# Alimentacion_y_perifericos.net
KiCad netlist of a schematic drawn in Altium Designer
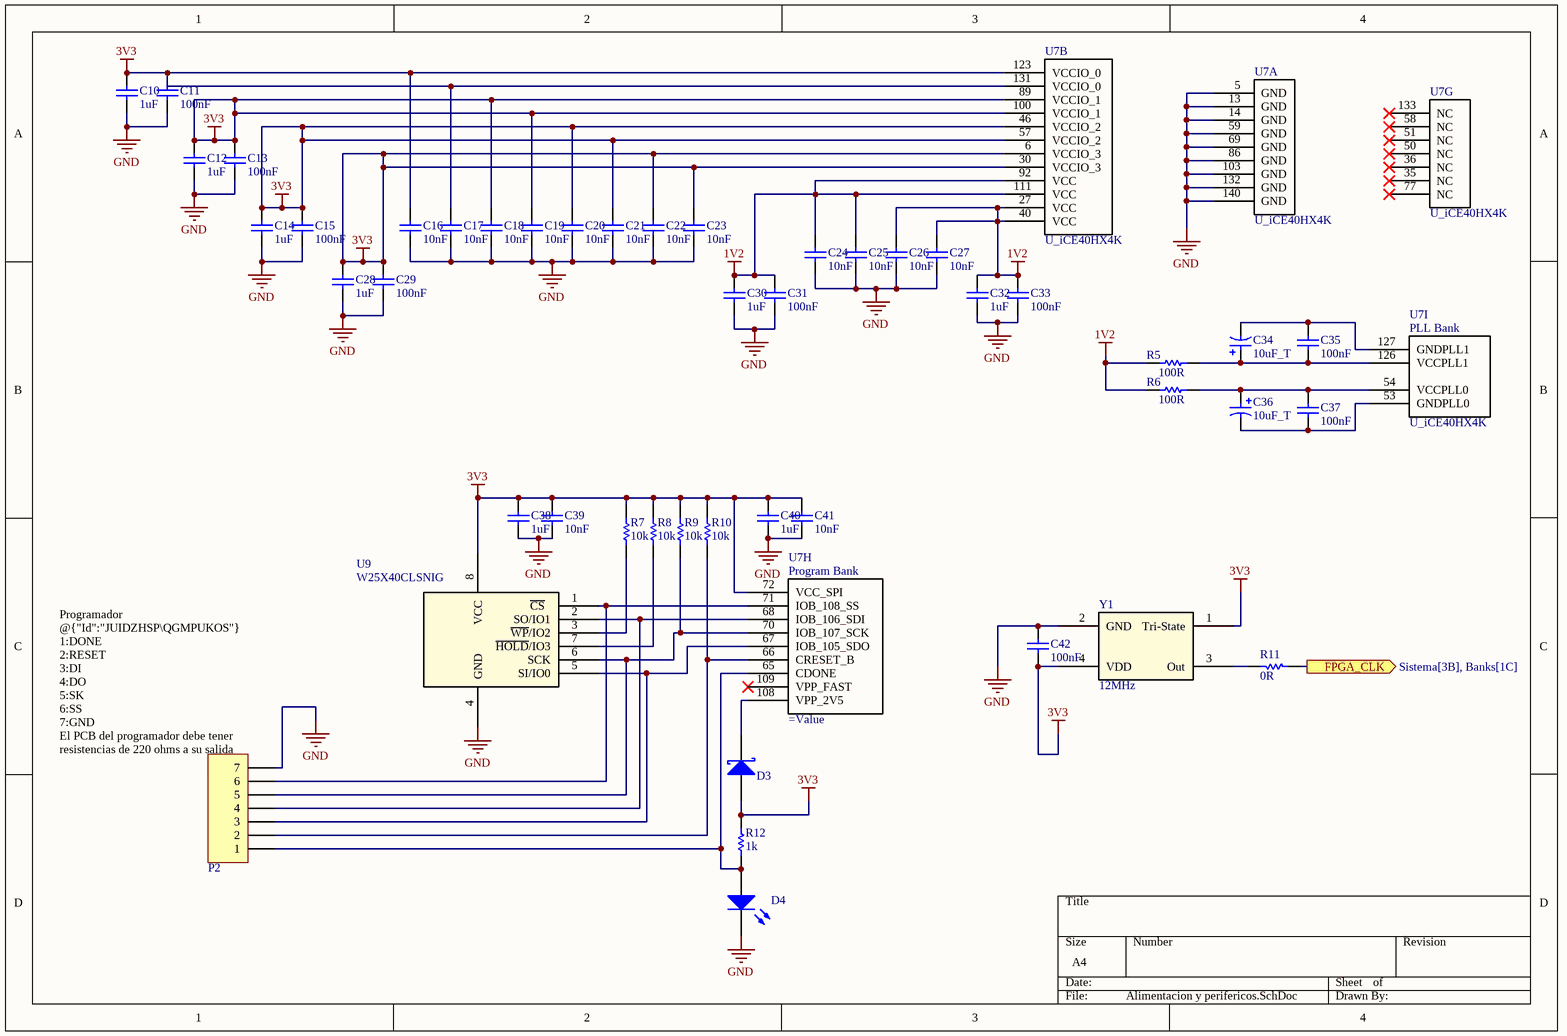
[diagram p0: Alimentacion y perifericos.SchDoc]

(export (version "E")
  (design (tool "Eeschema 10.0.6"))
  (components
    (comp (ref "C10")
      (value "1uF")
      (footprint "C_0805_2013_b")
      (description "Capacitor SMD 0805")
      (fields
        (field (name "MANUFACTURER") "Cal-Chip Electronics")
        (field (name "MANUFACTURER PART NUMBER") "GMC21X7R105K50NT")
      )
      (libsource (lib "MyLibraryV2") (part "C_1uF_50V_b"))
    )
    (comp (ref "C11")
      (value "100nF")
      (footprint "C_0805_2013_b")
      (description "Capacitor SMD 0805")
      (fields (field (name "TOLERANCE") "10%") (field (name "VOLTAGE") "50V"))
      (libsource (lib "MyLibraryV2") (part "C_100nF_50V_b"))
    )
    (comp (ref "C12")
      (value "1uF")
      (footprint "C_0805_2013_b")
      (description "Capacitor SMD 0805")
      (fields
        (field (name "MANUFACTURER") "Cal-Chip Electronics")
        (field (name "MANUFACTURER PART NUMBER") "GMC21X7R105K50NT")
      )
      (libsource (lib "MyLibraryV2") (part "C_1uF_50V_b"))
    )
    (comp (ref "C13")
      (value "100nF")
      (footprint "C_0805_2013_b")
      (description "Capacitor SMD 0805")
      (fields (field (name "TOLERANCE") "10%") (field (name "VOLTAGE") "50V"))
      (libsource (lib "MyLibraryV2") (part "C_100nF_50V_b"))
    )
    (comp (ref "C14")
      (value "1uF")
      (footprint "C_0805_2013_b")
      (description "Capacitor SMD 0805")
      (fields
        (field (name "MANUFACTURER") "Cal-Chip Electronics")
        (field (name "MANUFACTURER PART NUMBER") "GMC21X7R105K50NT")
      )
      (libsource (lib "MyLibraryV2") (part "C_1uF_50V_b"))
    )
    (comp (ref "C15")
      (value "100nF")
      (footprint "C_0805_2013_b")
      (description "Capacitor SMD 0805")
      (fields (field (name "TOLERANCE") "10%") (field (name "VOLTAGE") "50V"))
      (libsource (lib "MyLibraryV2") (part "C_100nF_50V_b"))
    )
    (comp (ref "C16")
      (value "10nF")
      (footprint "C_0805_2013_b")
      (description "Capacitor SMD 0805")
      (fields (field (name "TOLERANCE") "5%") (field (name "MANUFACTURER") "KEMET"))
      (libsource (lib "MyLibraryV2") (part "C_10nF_50V_b"))
    )
    (comp (ref "C17")
      (value "10nF")
      (footprint "C_0805_2013_b")
      (description "Capacitor SMD 0805")
      (fields (field (name "TOLERANCE") "5%") (field (name "MANUFACTURER") "KEMET"))
      (libsource (lib "MyLibraryV2") (part "C_10nF_50V_b"))
    )
    (comp (ref "C18")
      (value "10nF")
      (footprint "C_0805_2013_b")
      (description "Capacitor SMD 0805")
      (fields (field (name "TOLERANCE") "5%") (field (name "MANUFACTURER") "KEMET"))
      (libsource (lib "MyLibraryV2") (part "C_10nF_50V_b"))
    )
    (comp (ref "C19")
      (value "10nF")
      (footprint "C_0805_2013_b")
      (description "Capacitor SMD 0805")
      (fields (field (name "TOLERANCE") "5%") (field (name "MANUFACTURER") "KEMET"))
      (libsource (lib "MyLibraryV2") (part "C_10nF_50V_b"))
    )
    (comp (ref "C20")
      (value "10nF")
      (footprint "C_0805_2013_b")
      (description "Capacitor SMD 0805")
      (fields (field (name "TOLERANCE") "5%") (field (name "MANUFACTURER") "KEMET"))
      (libsource (lib "MyLibraryV2") (part "C_10nF_50V_b"))
    )
    (comp (ref "C21")
      (value "10nF")
      (footprint "C_0805_2013_b")
      (description "Capacitor SMD 0805")
      (fields (field (name "TOLERANCE") "5%") (field (name "MANUFACTURER") "KEMET"))
      (libsource (lib "MyLibraryV2") (part "C_10nF_50V_b"))
    )
    (comp (ref "C22")
      (value "10nF")
      (footprint "C_0805_2013_b")
      (description "Capacitor SMD 0805")
      (fields (field (name "TOLERANCE") "5%") (field (name "MANUFACTURER") "KEMET"))
      (libsource (lib "MyLibraryV2") (part "C_10nF_50V_b"))
    )
    (comp (ref "C23")
      (value "10nF")
      (footprint "C_0805_2013_b")
      (description "Capacitor SMD 0805")
      (fields (field (name "TOLERANCE") "5%") (field (name "MANUFACTURER") "KEMET"))
      (libsource (lib "MyLibraryV2") (part "C_10nF_50V_b"))
    )
    (comp (ref "C24")
      (value "10nF")
      (footprint "C_0805_2013_b")
      (description "Capacitor SMD 0805")
      (fields (field (name "TOLERANCE") "5%") (field (name "MANUFACTURER") "KEMET"))
      (libsource (lib "MyLibraryV2") (part "C_10nF_50V_b"))
    )
    (comp (ref "C25")
      (value "10nF")
      (footprint "C_0805_2013_b")
      (description "Capacitor SMD 0805")
      (fields (field (name "TOLERANCE") "5%") (field (name "MANUFACTURER") "KEMET"))
      (libsource (lib "MyLibraryV2") (part "C_10nF_50V_b"))
    )
    (comp (ref "C26")
      (value "10nF")
      (footprint "C_0805_2013_b")
      (description "Capacitor SMD 0805")
      (fields (field (name "TOLERANCE") "5%") (field (name "MANUFACTURER") "KEMET"))
      (libsource (lib "MyLibraryV2") (part "C_10nF_50V_b"))
    )
    (comp (ref "C27")
      (value "10nF")
      (footprint "C_0805_2013_b")
      (description "Capacitor SMD 0805")
      (fields (field (name "TOLERANCE") "5%") (field (name "MANUFACTURER") "KEMET"))
      (libsource (lib "MyLibraryV2") (part "C_10nF_50V_b"))
    )
    (comp (ref "C28")
      (value "1uF")
      (footprint "C_0805_2013_b")
      (description "Capacitor SMD 0805")
      (fields
        (field (name "MANUFACTURER") "Cal-Chip Electronics")
        (field (name "MANUFACTURER PART NUMBER") "GMC21X7R105K50NT")
      )
      (libsource (lib "MyLibraryV2") (part "C_1uF_50V_b"))
    )
    (comp (ref "C29")
      (value "100nF")
      (footprint "C_0805_2013_b")
      (description "Capacitor SMD 0805")
      (fields (field (name "TOLERANCE") "10%") (field (name "VOLTAGE") "50V"))
      (libsource (lib "MyLibraryV2") (part "C_100nF_50V_b"))
    )
    (comp (ref "C30")
      (value "1uF")
      (footprint "C_0805_2013_b")
      (description "Capacitor SMD 0805")
      (fields
        (field (name "MANUFACTURER") "Cal-Chip Electronics")
        (field (name "MANUFACTURER PART NUMBER") "GMC21X7R105K50NT")
      )
      (libsource (lib "MyLibraryV2") (part "C_1uF_50V_b"))
    )
    (comp (ref "C31")
      (value "100nF")
      (footprint "C_0805_2013_b")
      (description "Capacitor SMD 0805")
      (fields (field (name "TOLERANCE") "10%") (field (name "VOLTAGE") "50V"))
      (libsource (lib "MyLibraryV2") (part "C_100nF_50V_b"))
    )
    (comp (ref "C32")
      (value "1uF")
      (footprint "C_0805_2013_b")
      (description "Capacitor SMD 0805")
      (fields
        (field (name "MANUFACTURER") "Cal-Chip Electronics")
        (field (name "MANUFACTURER PART NUMBER") "GMC21X7R105K50NT")
      )
      (libsource (lib "MyLibraryV2") (part "C_1uF_50V_b"))
    )
    (comp (ref "C33")
      (value "100nF")
      (footprint "C_0805_2013_b")
      (description "Capacitor SMD 0805")
      (fields (field (name "TOLERANCE") "10%") (field (name "VOLTAGE") "50V"))
      (libsource (lib "MyLibraryV2") (part "C_100nF_50V_b"))
    )
    (comp (ref "C34")
      (value "10uF_T")
      (footprint "C_0805_2013_c")
      (description "Capacitor SMD 0805 Tant")
      (fields
        (field (name "MANUFACTURER") "Vishay")
        (field (name "MANUFACTURER PART NUMBER") "TMCP1A106MTRF")
      )
      (libsource (lib "MyLibraryV2") (part "C_10uF_10V_b"))
    )
    (comp (ref "C35")
      (value "100nF")
      (footprint "C_0805_2013_b")
      (description "Capacitor SMD 0805")
      (fields (field (name "TOLERANCE") "10%") (field (name "VOLTAGE") "50V"))
      (libsource (lib "MyLibraryV2") (part "C_100nF_50V_b"))
    )
    (comp (ref "C36")
      (value "10uF_T")
      (footprint "C_0805_2013_c")
      (description "Capacitor SMD 0805 Tant")
      (fields
        (field (name "MANUFACTURER") "Vishay")
        (field (name "MANUFACTURER PART NUMBER") "TMCP1A106MTRF")
      )
      (libsource (lib "MyLibraryV2") (part "C_10uF_10V_b"))
    )
    (comp (ref "C37")
      (value "100nF")
      (footprint "C_0805_2013_b")
      (description "Capacitor SMD 0805")
      (fields (field (name "TOLERANCE") "10%") (field (name "VOLTAGE") "50V"))
      (libsource (lib "MyLibraryV2") (part "C_100nF_50V_b"))
    )
    (comp (ref "C38")
      (value "1uF")
      (footprint "C_0805_2013_b")
      (description "Capacitor SMD 0805")
      (fields
        (field (name "MANUFACTURER") "Cal-Chip Electronics")
        (field (name "MANUFACTURER PART NUMBER") "GMC21X7R105K50NT")
      )
      (libsource (lib "MyLibraryV2") (part "C_1uF_50V_b"))
    )
    (comp (ref "C39")
      (value "10nF")
      (footprint "C_0805_2013_b")
      (description "Capacitor SMD 0805")
      (fields (field (name "TOLERANCE") "5%") (field (name "MANUFACTURER") "KEMET"))
      (libsource (lib "MyLibraryV2") (part "C_10nF_50V_b"))
    )
    (comp (ref "C40")
      (value "1uF")
      (footprint "C_0805_2013_b")
      (description "Capacitor SMD 0805")
      (fields
        (field (name "MANUFACTURER") "Cal-Chip Electronics")
        (field (name "MANUFACTURER PART NUMBER") "GMC21X7R105K50NT")
      )
      (libsource (lib "MyLibraryV2") (part "C_1uF_50V_b"))
    )
    (comp (ref "C41")
      (value "10nF")
      (footprint "C_0805_2013_b")
      (description "Capacitor SMD 0805")
      (fields (field (name "TOLERANCE") "5%") (field (name "MANUFACTURER") "KEMET"))
      (libsource (lib "MyLibraryV2") (part "C_10nF_50V_b"))
    )
    (comp (ref "C42")
      (value "100nF")
      (footprint "C_0805_2013_b")
      (description "Capacitor SMD 0805")
      (fields (field (name "TOLERANCE") "10%") (field (name "VOLTAGE") "50V"))
      (libsource (lib "MyLibraryV2") (part "C_100nF_50V_b"))
    )
    (comp (ref "D3")
      (value "SD0805S020S0R5")
      (footprint "D_SOD-123")
      (description "Diode SMD D_SD0805S020S0R5")
      (fields (field (name "MANUFACTURER") "Diodes") (field (name "MANUFACTURER PART NUMBER") "B550C-13-F"))
      (libsource (lib "Mi_lib") (part "D_SD0805S020S0R5"))
    )
    (comp (ref "D4")
      (value "GREEN")
      (footprint "D_LED_0805_2013")
      (description "(Modificar) Diode SMD 0805")
      (libsource (lib "MyLibraryV2") (part "D_LED_SMD_0805"))
    )
    (comp (ref "P2")
      (value "PROGRAM")
      (footprint "P_CON1X7")
      (description "Bornera 7")
      (libsource (lib "MyLibraryV2") (part "P_BORNERA 7"))
    )
    (comp (ref "R5")
      (value "100R")
      (footprint "R_0805_2012_a")
      (description "Resistor SMD 0805")
      (fields (field (name "TOLERANCE") "1%") (field (name "MANUFACTURER") "Vishay Dale"))
      (libsource (lib "MyLibraryV2") (part "R_100R_b"))
    )
    (comp (ref "R6")
      (value "100R")
      (footprint "R_0805_2012_a")
      (description "Resistor SMD 0805")
      (fields (field (name "TOLERANCE") "1%") (field (name "MANUFACTURER") "Vishay Dale"))
      (libsource (lib "MyLibraryV2") (part "R_100R_b"))
    )
    (comp (ref "R7")
      (value "10k")
      (footprint "R_0805_2012_a")
      (description "Resistor SMD 0805")
      (fields (field (name "TOLERANCE") "1%") (field (name "MANUFACTURER") "Yageo"))
      (libsource (lib "MyLibraryV2") (part "R_10k_b"))
    )
    (comp (ref "R8")
      (value "10k")
      (footprint "R_0805_2012_a")
      (description "Resistor SMD 0805")
      (fields (field (name "TOLERANCE") "1%") (field (name "MANUFACTURER") "Yageo"))
      (libsource (lib "MyLibraryV2") (part "R_10k_b"))
    )
    (comp (ref "R9")
      (value "10k")
      (footprint "R_0805_2012_a")
      (description "Resistor SMD 0805")
      (fields (field (name "TOLERANCE") "1%") (field (name "MANUFACTURER") "Yageo"))
      (libsource (lib "MyLibraryV2") (part "R_10k_b"))
    )
    (comp (ref "R10")
      (value "10k")
      (footprint "R_0805_2012_a")
      (description "Resistor SMD 0805")
      (fields (field (name "TOLERANCE") "1%") (field (name "MANUFACTURER") "Yageo"))
      (libsource (lib "MyLibraryV2") (part "R_10k_b"))
    )
    (comp (ref "R11")
      (value "0R")
      (footprint "R_0805_2012_a")
      (description "Resistor SMD 0805")
      (fields
        (field (name "MANUFACTURER") "Stackpole Electronics")
        (field (name "MANUFACTURER PART NUMBER") "RMCF0805ZT0R00")
      )
      (libsource (lib "MyLibraryV2") (part "R_0R_b"))
    )
    (comp (ref "R12")
      (value "1k")
      (footprint "R_0805_2012_a")
      (description "Resistor SMD 0805")
      (fields (field (name "TOLERANCE") "1%") (field (name "MANUFACTURER") "Bourns"))
      (libsource (lib "MyLibraryV2") (part "R_1k_b"))
    )
    (comp (ref "U7")
      (value "U_iCE40HX4K")
      (footprint "U_TQFP-144")
      (libsource (lib "") (part "U_iCE40HX4K_4"))
    )
    (comp (ref "U9")
      (value "W25X40CLSNIG")
      (footprint "U_SOIC-8_2")
      (libsource (lib "Mi_lib") (part "U_W25X40CLSNIG"))
    )
    (comp (ref "Y1")
      (value "12MHz")
      (footprint "Y_SMD-XTAL-12MHz")
      (libsource (lib "Mi_lib") (part "Y_12MHZ"))
    )
  )
  (nets
    (net (code "1") (name "/FPGA_CLK") (class "Default")
      (node (ref "R11") (pin "1") (pinfunction "1_1") (pintype "passive"))
    )
    (net (code "2") (name "1V2") (class "Default")
      (node (ref "C24") (pin "1") (pinfunction "1_1") (pintype "passive"))
      (node (ref "C25") (pin "1") (pinfunction "1_1") (pintype "passive"))
      (node (ref "C26") (pin "1") (pinfunction "1_1") (pintype "passive"))
      (node (ref "C27") (pin "1") (pinfunction "1_1") (pintype "passive"))
      (node (ref "C30") (pin "2") (pinfunction "2_2") (pintype "passive"))
      (node (ref "C31") (pin "2") (pinfunction "2_2") (pintype "passive"))
      (node (ref "C32") (pin "2") (pinfunction "2_2") (pintype "passive"))
      (node (ref "C33") (pin "2") (pinfunction "2_2") (pintype "passive"))
      (node (ref "R5") (pin "1") (pinfunction "1_1") (pintype "passive"))
      (node (ref "R6") (pin "1") (pinfunction "1_1") (pintype "passive"))
      (node (ref "U7") (pin "111") (pinfunction "VCC_111") (pintype "passive"))
      (node (ref "U7") (pin "27") (pinfunction "VCC_27") (pintype "passive"))
      (node (ref "U7") (pin "40") (pinfunction "VCC_40") (pintype "passive"))
      (node (ref "U7") (pin "92") (pinfunction "VCC_92") (pintype "passive"))
    )
    (net (code "3") (name "3V3") (class "Default")
      (node (ref "C10") (pin "2") (pinfunction "2_2") (pintype "passive"))
      (node (ref "C11") (pin "2") (pinfunction "2_2") (pintype "passive"))
      (node (ref "C12") (pin "2") (pinfunction "2_2") (pintype "passive"))
      (node (ref "C13") (pin "2") (pinfunction "2_2") (pintype "passive"))
      (node (ref "C14") (pin "2") (pinfunction "2_2") (pintype "passive"))
      (node (ref "C15") (pin "2") (pinfunction "2_2") (pintype "passive"))
      (node (ref "C16") (pin "1") (pinfunction "1_1") (pintype "passive"))
      (node (ref "C17") (pin "1") (pinfunction "1_1") (pintype "passive"))
      (node (ref "C18") (pin "1") (pinfunction "1_1") (pintype "passive"))
      (node (ref "C19") (pin "1") (pinfunction "1_1") (pintype "passive"))
      (node (ref "C20") (pin "1") (pinfunction "1_1") (pintype "passive"))
      (node (ref "C21") (pin "1") (pinfunction "1_1") (pintype "passive"))
      (node (ref "C22") (pin "1") (pinfunction "1_1") (pintype "passive"))
      (node (ref "C23") (pin "1") (pinfunction "1_1") (pintype "passive"))
      (node (ref "C28") (pin "2") (pinfunction "2_2") (pintype "passive"))
      (node (ref "C29") (pin "2") (pinfunction "2_2") (pintype "passive"))
      (node (ref "C38") (pin "2") (pinfunction "2_2") (pintype "passive"))
      (node (ref "C39") (pin "2") (pinfunction "2_2") (pintype "passive"))
      (node (ref "C40") (pin "2") (pinfunction "2_2") (pintype "passive"))
      (node (ref "C41") (pin "2") (pinfunction "2_2") (pintype "passive"))
      (node (ref "C42") (pin "1") (pinfunction "1_1") (pintype "passive"))
      (node (ref "D3") (pin "2") (pinfunction "A_2") (pintype "passive"))
      (node (ref "R10") (pin "2") (pinfunction "2_2") (pintype "passive"))
      (node (ref "R12") (pin "1") (pinfunction "1_1") (pintype "passive"))
      (node (ref "R7") (pin "2") (pinfunction "2_2") (pintype "passive"))
      (node (ref "R8") (pin "2") (pinfunction "2_2") (pintype "passive"))
      (node (ref "R9") (pin "2") (pinfunction "2_2") (pintype "passive"))
      (node (ref "U7") (pin "100") (pinfunction "VCCIO_1_100") (pintype "passive"))
      (node (ref "U7") (pin "123") (pinfunction "VCCIO_0_123") (pintype "passive"))
      (node (ref "U7") (pin "131") (pinfunction "VCCIO_0_131") (pintype "passive"))
      (node (ref "U7") (pin "30") (pinfunction "VCCIO_3_30") (pintype "passive"))
      (node (ref "U7") (pin "46") (pinfunction "VCCIO_2_46") (pintype "passive"))
      (node (ref "U7") (pin "57") (pinfunction "VCCIO_2_57") (pintype "passive"))
      (node (ref "U7") (pin "6") (pinfunction "VCCIO_3_6") (pintype "passive"))
      (node (ref "U7") (pin "72") (pinfunction "VCC_SPI_72") (pintype "passive"))
      (node (ref "U7") (pin "89") (pinfunction "VCCIO_1_89") (pintype "passive"))
      (node (ref "U9") (pin "8") (pinfunction "VCC_8") (pintype "passive"))
      (node (ref "Y1") (pin "1") (pinfunction "Tri-State_1") (pintype "passive"))
      (node (ref "Y1") (pin "4") (pinfunction "VDD_4") (pintype "passive"))
    )
    (net (code "4") (name "GND") (class "Default")
      (node (ref "C10") (pin "1") (pinfunction "1_1") (pintype "passive"))
      (node (ref "C11") (pin "1") (pinfunction "1_1") (pintype "passive"))
      (node (ref "C12") (pin "1") (pinfunction "1_1") (pintype "passive"))
      (node (ref "C13") (pin "1") (pinfunction "1_1") (pintype "passive"))
      (node (ref "C14") (pin "1") (pinfunction "1_1") (pintype "passive"))
      (node (ref "C15") (pin "1") (pinfunction "1_1") (pintype "passive"))
      (node (ref "C16") (pin "2") (pinfunction "2_2") (pintype "passive"))
      (node (ref "C17") (pin "2") (pinfunction "2_2") (pintype "passive"))
      (node (ref "C18") (pin "2") (pinfunction "2_2") (pintype "passive"))
      (node (ref "C19") (pin "2") (pinfunction "2_2") (pintype "passive"))
      (node (ref "C20") (pin "2") (pinfunction "2_2") (pintype "passive"))
      (node (ref "C21") (pin "2") (pinfunction "2_2") (pintype "passive"))
      (node (ref "C22") (pin "2") (pinfunction "2_2") (pintype "passive"))
      (node (ref "C23") (pin "2") (pinfunction "2_2") (pintype "passive"))
      (node (ref "C24") (pin "2") (pinfunction "2_2") (pintype "passive"))
      (node (ref "C25") (pin "2") (pinfunction "2_2") (pintype "passive"))
      (node (ref "C26") (pin "2") (pinfunction "2_2") (pintype "passive"))
      (node (ref "C27") (pin "2") (pinfunction "2_2") (pintype "passive"))
      (node (ref "C28") (pin "1") (pinfunction "1_1") (pintype "passive"))
      (node (ref "C29") (pin "1") (pinfunction "1_1") (pintype "passive"))
      (node (ref "C30") (pin "1") (pinfunction "1_1") (pintype "passive"))
      (node (ref "C31") (pin "1") (pinfunction "1_1") (pintype "passive"))
      (node (ref "C32") (pin "1") (pinfunction "1_1") (pintype "passive"))
      (node (ref "C33") (pin "1") (pinfunction "1_1") (pintype "passive"))
      (node (ref "C38") (pin "1") (pinfunction "1_1") (pintype "passive"))
      (node (ref "C39") (pin "1") (pinfunction "1_1") (pintype "passive"))
      (node (ref "C40") (pin "1") (pinfunction "1_1") (pintype "passive"))
      (node (ref "C41") (pin "1") (pinfunction "1_1") (pintype "passive"))
      (node (ref "C42") (pin "2") (pinfunction "2_2") (pintype "passive"))
      (node (ref "D4") (pin "1") (pinfunction "K_1") (pintype "passive"))
      (node (ref "P2") (pin "7") (pinfunction "7_7") (pintype "passive"))
      (node (ref "U7") (pin "103") (pinfunction "GND_103") (pintype "passive"))
      (node (ref "U7") (pin "13") (pinfunction "GND_13") (pintype "passive"))
      (node (ref "U7") (pin "132") (pinfunction "GND_132") (pintype "passive"))
      (node (ref "U7") (pin "14") (pinfunction "GND_14") (pintype "passive"))
      (node (ref "U7") (pin "140") (pinfunction "GND_140") (pintype "passive"))
      (node (ref "U7") (pin "5") (pinfunction "GND_5") (pintype "passive"))
      (node (ref "U7") (pin "59") (pinfunction "GND_59") (pintype "passive"))
      (node (ref "U7") (pin "69") (pinfunction "GND_69") (pintype "passive"))
      (node (ref "U7") (pin "86") (pinfunction "GND_86") (pintype "passive"))
      (node (ref "U9") (pin "4") (pinfunction "GND_4") (pintype "passive"))
      (node (ref "Y1") (pin "2") (pinfunction "GND_2") (pintype "passive"))
    )
    (net (code "5") (name "Net-(D3-K)") (class "Default")
      (node (ref "D3") (pin "1") (pinfunction "K_1") (pintype "passive"))
      (node (ref "U7") (pin "108") (pinfunction "VPP_2V5_108") (pintype "passive"))
    )
    (net (code "6") (name "Net-(D4-A)") (class "Default")
      (node (ref "D4") (pin "2") (pinfunction "A_2") (pintype "passive"))
      (node (ref "P2") (pin "1") (pinfunction "1_1") (pintype "passive"))
      (node (ref "R12") (pin "2") (pinfunction "2_2") (pintype "passive"))
      (node (ref "U7") (pin "65") (pinfunction "CDONE_65") (pintype "passive"))
    )
    (net (code "7") (name "Net-(U7H-CRESET_B)") (class "Default")
      (node (ref "P2") (pin "2") (pinfunction "2_2") (pintype "passive"))
      (node (ref "R10") (pin "1") (pinfunction "1_1") (pintype "passive"))
      (node (ref "U7") (pin "66") (pinfunction "CRESET_B_66") (pintype "passive"))
    )
    (net (code "8") (name "Net-(U7H-IOB_105_SDO)") (class "Default")
      (node (ref "P2") (pin "3") (pinfunction "3_3") (pintype "passive"))
      (node (ref "U7") (pin "67") (pinfunction "IOB_105_SDO_67") (pintype "passive"))
      (node (ref "U9") (pin "5") (pinfunction "SI/IO0_5") (pintype "passive"))
    )
    (net (code "9") (name "Net-(U7H-IOB_106_SDI)") (class "Default")
      (node (ref "P2") (pin "4") (pinfunction "4_4") (pintype "passive"))
      (node (ref "U7") (pin "68") (pinfunction "IOB_106_SDI_68") (pintype "passive"))
      (node (ref "U9") (pin "2") (pinfunction "SO/IO1_2") (pintype "passive"))
    )
    (net (code "10") (name "Net-(U7H-IOB_107_SCK)") (class "Default")
      (node (ref "P2") (pin "5") (pinfunction "5_5") (pintype "passive"))
      (node (ref "R9") (pin "1") (pinfunction "1_1") (pintype "passive"))
      (node (ref "U7") (pin "70") (pinfunction "IOB_107_SCK_70") (pintype "passive"))
      (node (ref "U9") (pin "6") (pinfunction "SCK_6") (pintype "passive"))
    )
    (net (code "11") (name "Net-(U7H-IOB_108_SS)") (class "Default")
      (node (ref "P2") (pin "6") (pinfunction "6_6") (pintype "passive"))
      (node (ref "U7") (pin "71") (pinfunction "IOB_108_SS_71") (pintype "passive"))
      (node (ref "U9") (pin "1") (pinfunction "~{CS}_1") (pintype "passive"))
    )
    (net (code "12") (name "Net-(U7I-GNDPLL0)") (class "Default")
      (node (ref "C36") (pin "2") (pinfunction "2_2") (pintype "passive"))
      (node (ref "C37") (pin "2") (pinfunction "2_2") (pintype "passive"))
      (node (ref "U7") (pin "53") (pinfunction "GNDPLL0_53") (pintype "passive"))
    )
    (net (code "13") (name "Net-(U7I-GNDPLL1)") (class "Default")
      (node (ref "C34") (pin "2") (pinfunction "2_2") (pintype "passive"))
      (node (ref "C35") (pin "2") (pinfunction "2_2") (pintype "passive"))
      (node (ref "U7") (pin "127") (pinfunction "GNDPLL1_127") (pintype "passive"))
    )
    (net (code "14") (name "Net-(U7I-VCCPLL0)") (class "Default")
      (node (ref "C36") (pin "1") (pinfunction "1_1") (pintype "passive"))
      (node (ref "C37") (pin "1") (pinfunction "1_1") (pintype "passive"))
      (node (ref "R6") (pin "2") (pinfunction "2_2") (pintype "passive"))
      (node (ref "U7") (pin "54") (pinfunction "VCCPLL0_54") (pintype "passive"))
    )
    (net (code "15") (name "Net-(U7I-VCCPLL1)") (class "Default")
      (node (ref "C34") (pin "1") (pinfunction "1_1") (pintype "passive"))
      (node (ref "C35") (pin "1") (pinfunction "1_1") (pintype "passive"))
      (node (ref "R5") (pin "2") (pinfunction "2_2") (pintype "passive"))
      (node (ref "U7") (pin "126") (pinfunction "VCCPLL1_126") (pintype "passive"))
    )
    (net (code "16") (name "Net-(U9-~{HOLD}{slash}IO3)") (class "Default")
      (node (ref "R8") (pin "1") (pinfunction "1_1") (pintype "passive"))
      (node (ref "U9") (pin "7") (pinfunction "~{HOLD}/IO3_7") (pintype "passive"))
    )
    (net (code "17") (name "Net-(U9-~{WP}{slash}IO2)") (class "Default")
      (node (ref "R7") (pin "1") (pinfunction "1_1") (pintype "passive"))
      (node (ref "U9") (pin "3") (pinfunction "~{WP}/IO2_3") (pintype "passive"))
    )
    (net (code "18") (name "Net-(Y1-Out)") (class "Default")
      (node (ref "R11") (pin "2") (pinfunction "2_2") (pintype "passive"))
      (node (ref "Y1") (pin "3") (pinfunction "Out_3") (pintype "passive"))
    )
    (net (code "19") (name "unconnected-(U7G-NC-Pad35)") (class "Default")
      (node (ref "U7") (pin "35") (pinfunction "NC_35") (pintype "passive+no_connect"))
    )
    (net (code "20") (name "unconnected-(U7G-NC-Pad36)") (class "Default")
      (node (ref "U7") (pin "36") (pinfunction "NC_36") (pintype "passive+no_connect"))
    )
    (net (code "21") (name "unconnected-(U7G-NC-Pad50)") (class "Default")
      (node (ref "U7") (pin "50") (pinfunction "NC_50") (pintype "passive+no_connect"))
    )
    (net (code "22") (name "unconnected-(U7G-NC-Pad51)") (class "Default")
      (node (ref "U7") (pin "51") (pinfunction "NC_51") (pintype "passive+no_connect"))
    )
    (net (code "23") (name "unconnected-(U7G-NC-Pad58)") (class "Default")
      (node (ref "U7") (pin "58") (pinfunction "NC_58") (pintype "passive+no_connect"))
    )
    (net (code "24") (name "unconnected-(U7G-NC-Pad77)") (class "Default")
      (node (ref "U7") (pin "77") (pinfunction "NC_77") (pintype "passive+no_connect"))
    )
    (net (code "25") (name "unconnected-(U7G-NC-Pad133)") (class "Default")
      (node (ref "U7") (pin "133") (pinfunction "NC_133") (pintype "passive+no_connect"))
    )
    (net (code "26") (name "unconnected-(U7H-VPP_FAST-Pad109)") (class "Default")
      (node (ref "U7") (pin "109") (pinfunction "VPP_FAST_109") (pintype "passive+no_connect"))
    )
  )
)
